# ind_8700.net
KiCad netlist of a schematic drawn in Altium Designer
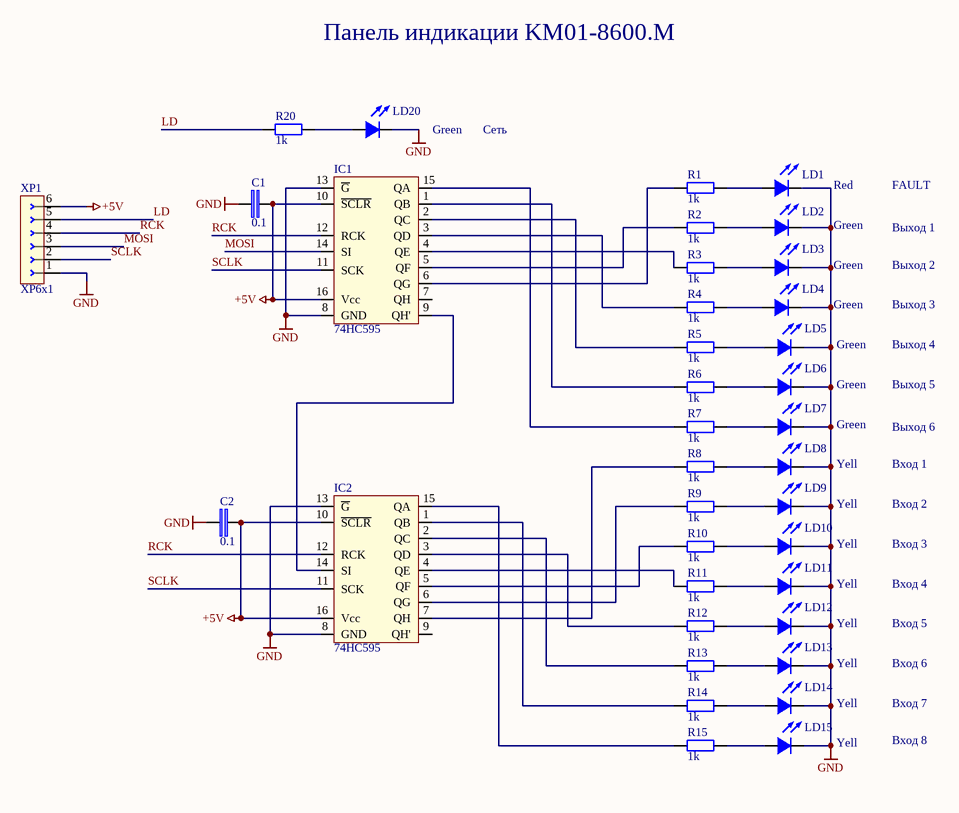
[diagram p0: ind_8700.SchDoc]

(export (version "E")
  (design (tool "Eeschema 10.0.6"))
  (components
    (comp (ref "C1") (value "0.1") (footprint "CAPC2113X13N_0805") (libsource (lib "Lib_my1") (part "cap_1")))
    (comp (ref "C2") (value "0.1") (footprint "CAPC2113X13N_0805") (libsource (lib "Lib_my1") (part "cap_1")))
    (comp (ref "IC1")
      (value "74HC595")
      (footprint "SOIC_16_74hc")
      (libsource (lib "Lib_my1") (part "74hc595_1"))
    )
    (comp (ref "IC2")
      (value "74HC595")
      (footprint "SOIC_16_74hc")
      (libsource (lib "Lib_my1") (part "74hc595_1"))
    )
    (comp (ref "LD1") (value "Red") (footprint "LED_3") (libsource (lib "Lib_my1") (part "LED_1")))
    (comp (ref "LD2") (value "Green") (footprint "LED_3") (libsource (lib "Lib_my1") (part "LED_1")))
    (comp (ref "LD3") (value "Green") (footprint "LED_3") (libsource (lib "Lib_my1") (part "LED_1")))
    (comp (ref "LD4") (value "Green") (footprint "LED_3") (libsource (lib "Lib_my1") (part "LED_1")))
    (comp (ref "LD5") (value "Green") (footprint "LED_3") (libsource (lib "Lib_my1") (part "LED_1")))
    (comp (ref "LD6") (value "Green") (footprint "LED_3") (libsource (lib "Lib_my1") (part "LED_1")))
    (comp (ref "LD7") (value "Green") (footprint "LED_3") (libsource (lib "Lib_my1") (part "LED_1")))
    (comp (ref "LD8") (value "Yell") (footprint "LED_3") (libsource (lib "Lib_my1") (part "LED_1")))
    (comp (ref "LD9") (value "Yell") (footprint "LED_3") (libsource (lib "Lib_my1") (part "LED_1")))
    (comp (ref "LD10") (value "Yell") (footprint "LED_3") (libsource (lib "Lib_my1") (part "LED_1")))
    (comp (ref "LD11") (value "Yell") (footprint "LED_3") (libsource (lib "Lib_my1") (part "LED_1")))
    (comp (ref "LD12") (value "Yell") (footprint "LED_3") (libsource (lib "Lib_my1") (part "LED_1")))
    (comp (ref "LD13") (value "Yell") (footprint "LED_3") (libsource (lib "Lib_my1") (part "LED_1")))
    (comp (ref "LD14") (value "Yell") (footprint "LED_3") (libsource (lib "Lib_my1") (part "LED_1")))
    (comp (ref "LD15") (value "Yell") (footprint "LED_3") (libsource (lib "Lib_my1") (part "LED_1")))
    (comp (ref "LD20") (value "Green") (footprint "LED_3") (libsource (lib "Lib_my1") (part "LED_1")))
    (comp (ref "R1") (value "1k") (footprint "RESC2113X0805N") (libsource (lib "Lib_my1") (part "rez_1")))
    (comp (ref "R2") (value "1k") (footprint "RESC2113X0805N") (libsource (lib "Lib_my1") (part "rez_1")))
    (comp (ref "R3") (value "1k") (footprint "RESC2113X0805N") (libsource (lib "Lib_my1") (part "rez_1")))
    (comp (ref "R4") (value "1k") (footprint "RESC2113X0805N") (libsource (lib "Lib_my1") (part "rez_1")))
    (comp (ref "R5") (value "1k") (footprint "RESC2113X0805N") (libsource (lib "Lib_my1") (part "rez_1")))
    (comp (ref "R6") (value "1k") (footprint "RESC2113X0805N") (libsource (lib "Lib_my1") (part "rez_1")))
    (comp (ref "R7") (value "1k") (footprint "RESC2113X0805N") (libsource (lib "Lib_my1") (part "rez_1")))
    (comp (ref "R8") (value "1k") (footprint "RESC2113X0805N") (libsource (lib "Lib_my1") (part "rez_1")))
    (comp (ref "R9") (value "1k") (footprint "RESC2113X0805N") (libsource (lib "Lib_my1") (part "rez_1")))
    (comp (ref "R10") (value "1k") (footprint "RESC2113X0805N") (libsource (lib "Lib_my1") (part "rez_1")))
    (comp (ref "R11") (value "1k") (footprint "RESC2113X0805N") (libsource (lib "Lib_my1") (part "rez_1")))
    (comp (ref "R12") (value "1k") (footprint "RESC2113X0805N") (libsource (lib "Lib_my1") (part "rez_1")))
    (comp (ref "R13") (value "1k") (footprint "RESC2113X0805N") (libsource (lib "Lib_my1") (part "rez_1")))
    (comp (ref "R14") (value "1k") (footprint "RESC2113X0805N") (libsource (lib "Lib_my1") (part "rez_1")))
    (comp (ref "R15") (value "1k") (footprint "RESC2113X0805N") (libsource (lib "Lib_my1") (part "rez_1")))
    (comp (ref "R20") (value "1k") (footprint "RESC2113X0805N") (libsource (lib "Lib_my1") (part "rez_1")))
    (comp (ref "XP1")
      (value "XP6x1")
      (footprint "Connect6_1")
      (libsource (lib "Lib_my1") (part "Connect6_1"))
    )
  )
  (nets
    (net (code "1") (name "+5V") (class "Default")
      (node (ref "C1") (pin "2") (pinfunction "2_2") (pintype "passive"))
      (node (ref "C2") (pin "2") (pinfunction "2_2") (pintype "passive"))
      (node (ref "IC1") (pin "10") (pinfunction "~{SCLR}_10") (pintype "passive"))
      (node (ref "IC1") (pin "16") (pinfunction "Vcc_16") (pintype "passive"))
      (node (ref "IC2") (pin "10") (pinfunction "~{SCLR}_10") (pintype "passive"))
      (node (ref "IC2") (pin "16") (pinfunction "Vcc_16") (pintype "passive"))
      (node (ref "XP1") (pin "6") (pinfunction "6_6") (pintype "passive"))
    )
    (net (code "2") (name "/LD") (class "Default")
      (node (ref "R20") (pin "2") (pinfunction "2_2") (pintype "passive"))
      (node (ref "XP1") (pin "5") (pinfunction "5_5") (pintype "passive"))
    )
    (net (code "3") (name "/MOSI") (class "Default")
      (node (ref "IC1") (pin "14") (pinfunction "SI_14") (pintype "passive"))
      (node (ref "XP1") (pin "3") (pinfunction "3_3") (pintype "passive"))
    )
    (net (code "4") (name "/RCK") (class "Default")
      (node (ref "IC1") (pin "12") (pinfunction "RCK_12") (pintype "passive"))
      (node (ref "IC2") (pin "12") (pinfunction "RCK_12") (pintype "passive"))
      (node (ref "XP1") (pin "4") (pinfunction "4_4") (pintype "passive"))
    )
    (net (code "5") (name "/SCLK") (class "Default")
      (node (ref "IC1") (pin "11") (pinfunction "SCK_11") (pintype "passive"))
      (node (ref "IC2") (pin "11") (pinfunction "SCK_11") (pintype "passive"))
      (node (ref "XP1") (pin "2") (pinfunction "2_2") (pintype "passive"))
    )
    (net (code "6") (name "GND") (class "Default")
      (node (ref "C1") (pin "1") (pinfunction "1_1") (pintype "passive"))
      (node (ref "C2") (pin "1") (pinfunction "1_1") (pintype "passive"))
      (node (ref "IC1") (pin "13") (pinfunction "G_13") (pintype "passive"))
      (node (ref "IC1") (pin "8") (pinfunction "GND_8") (pintype "passive"))
      (node (ref "IC2") (pin "13") (pinfunction "G_13") (pintype "passive"))
      (node (ref "IC2") (pin "8") (pinfunction "GND_8") (pintype "passive"))
      (node (ref "LD1") (pin "2") (pinfunction "2_2") (pintype "passive"))
      (node (ref "LD10") (pin "2") (pinfunction "2_2") (pintype "passive"))
      (node (ref "LD11") (pin "2") (pinfunction "2_2") (pintype "passive"))
      (node (ref "LD12") (pin "2") (pinfunction "2_2") (pintype "passive"))
      (node (ref "LD13") (pin "2") (pinfunction "2_2") (pintype "passive"))
      (node (ref "LD14") (pin "2") (pinfunction "2_2") (pintype "passive"))
      (node (ref "LD15") (pin "2") (pinfunction "2_2") (pintype "passive"))
      (node (ref "LD2") (pin "2") (pinfunction "2_2") (pintype "passive"))
      (node (ref "LD20") (pin "2") (pinfunction "2_2") (pintype "passive"))
      (node (ref "LD3") (pin "2") (pinfunction "2_2") (pintype "passive"))
      (node (ref "LD4") (pin "2") (pinfunction "2_2") (pintype "passive"))
      (node (ref "LD5") (pin "2") (pinfunction "2_2") (pintype "passive"))
      (node (ref "LD6") (pin "2") (pinfunction "2_2") (pintype "passive"))
      (node (ref "LD7") (pin "2") (pinfunction "2_2") (pintype "passive"))
      (node (ref "LD8") (pin "2") (pinfunction "2_2") (pintype "passive"))
      (node (ref "LD9") (pin "2") (pinfunction "2_2") (pintype "passive"))
      (node (ref "XP1") (pin "1") (pinfunction "1_1") (pintype "passive"))
    )
    (net (code "7") (name "Net-(IC1-QA)") (class "Default")
      (node (ref "IC1") (pin "15") (pinfunction "QA_15") (pintype "passive"))
      (node (ref "R7") (pin "2") (pinfunction "2_2") (pintype "passive"))
    )
    (net (code "8") (name "Net-(IC1-QB)") (class "Default")
      (node (ref "IC1") (pin "1") (pinfunction "QB_1") (pintype "passive"))
      (node (ref "R6") (pin "2") (pinfunction "2_2") (pintype "passive"))
    )
    (net (code "9") (name "Net-(IC1-QC)") (class "Default")
      (node (ref "IC1") (pin "2") (pinfunction "QC_2") (pintype "passive"))
      (node (ref "R5") (pin "2") (pinfunction "2_2") (pintype "passive"))
    )
    (net (code "10") (name "Net-(IC1-QD)") (class "Default")
      (node (ref "IC1") (pin "3") (pinfunction "QD_3") (pintype "passive"))
      (node (ref "R4") (pin "2") (pinfunction "2_2") (pintype "passive"))
    )
    (net (code "11") (name "Net-(IC1-QE)") (class "Default")
      (node (ref "IC1") (pin "4") (pinfunction "QE_4") (pintype "passive"))
      (node (ref "R3") (pin "2") (pinfunction "2_2") (pintype "passive"))
    )
    (net (code "12") (name "Net-(IC1-QF)") (class "Default")
      (node (ref "IC1") (pin "5") (pinfunction "QF_5") (pintype "passive"))
      (node (ref "R2") (pin "2") (pinfunction "2_2") (pintype "passive"))
    )
    (net (code "13") (name "Net-(IC1-QG)") (class "Default")
      (node (ref "IC1") (pin "6") (pinfunction "QG_6") (pintype "passive"))
      (node (ref "R1") (pin "2") (pinfunction "2_2") (pintype "passive"))
    )
    (net (code "14") (name "Net-(IC1-QH')") (class "Default")
      (node (ref "IC1") (pin "9") (pinfunction "QH'_9") (pintype "passive"))
      (node (ref "IC2") (pin "14") (pinfunction "SI_14") (pintype "passive"))
    )
    (net (code "15") (name "Net-(IC2-QA)") (class "Default")
      (node (ref "IC2") (pin "15") (pinfunction "QA_15") (pintype "passive"))
      (node (ref "R15") (pin "2") (pinfunction "2_2") (pintype "passive"))
    )
    (net (code "16") (name "Net-(IC2-QB)") (class "Default")
      (node (ref "IC2") (pin "1") (pinfunction "QB_1") (pintype "passive"))
      (node (ref "R14") (pin "2") (pinfunction "2_2") (pintype "passive"))
    )
    (net (code "17") (name "Net-(IC2-QC)") (class "Default")
      (node (ref "IC2") (pin "2") (pinfunction "QC_2") (pintype "passive"))
      (node (ref "R13") (pin "2") (pinfunction "2_2") (pintype "passive"))
    )
    (net (code "18") (name "Net-(IC2-QD)") (class "Default")
      (node (ref "IC2") (pin "3") (pinfunction "QD_3") (pintype "passive"))
      (node (ref "R12") (pin "2") (pinfunction "2_2") (pintype "passive"))
    )
    (net (code "19") (name "Net-(IC2-QE)") (class "Default")
      (node (ref "IC2") (pin "4") (pinfunction "QE_4") (pintype "passive"))
      (node (ref "R11") (pin "2") (pinfunction "2_2") (pintype "passive"))
    )
    (net (code "20") (name "Net-(IC2-QF)") (class "Default")
      (node (ref "IC2") (pin "5") (pinfunction "QF_5") (pintype "passive"))
      (node (ref "R10") (pin "2") (pinfunction "2_2") (pintype "passive"))
    )
    (net (code "21") (name "Net-(IC2-QG)") (class "Default")
      (node (ref "IC2") (pin "6") (pinfunction "QG_6") (pintype "passive"))
      (node (ref "R9") (pin "2") (pinfunction "2_2") (pintype "passive"))
    )
    (net (code "22") (name "Net-(IC2-QH)") (class "Default")
      (node (ref "IC2") (pin "7") (pinfunction "QH_7") (pintype "passive"))
      (node (ref "R8") (pin "2") (pinfunction "2_2") (pintype "passive"))
    )
    (net (code "23") (name "Net-(LD1-Pad1)") (class "Default")
      (node (ref "LD1") (pin "1") (pinfunction "1_1") (pintype "passive"))
      (node (ref "R1") (pin "1") (pinfunction "1_1") (pintype "passive"))
    )
    (net (code "24") (name "Net-(LD2-Pad1)") (class "Default")
      (node (ref "LD2") (pin "1") (pinfunction "1_1") (pintype "passive"))
      (node (ref "R2") (pin "1") (pinfunction "1_1") (pintype "passive"))
    )
    (net (code "25") (name "Net-(LD3-Pad1)") (class "Default")
      (node (ref "LD3") (pin "1") (pinfunction "1_1") (pintype "passive"))
      (node (ref "R3") (pin "1") (pinfunction "1_1") (pintype "passive"))
    )
    (net (code "26") (name "Net-(LD4-Pad1)") (class "Default")
      (node (ref "LD4") (pin "1") (pinfunction "1_1") (pintype "passive"))
      (node (ref "R4") (pin "1") (pinfunction "1_1") (pintype "passive"))
    )
    (net (code "27") (name "Net-(LD5-Pad1)") (class "Default")
      (node (ref "LD5") (pin "1") (pinfunction "1_1") (pintype "passive"))
      (node (ref "R5") (pin "1") (pinfunction "1_1") (pintype "passive"))
    )
    (net (code "28") (name "Net-(LD6-Pad1)") (class "Default")
      (node (ref "LD6") (pin "1") (pinfunction "1_1") (pintype "passive"))
      (node (ref "R6") (pin "1") (pinfunction "1_1") (pintype "passive"))
    )
    (net (code "29") (name "Net-(LD7-Pad1)") (class "Default")
      (node (ref "LD7") (pin "1") (pinfunction "1_1") (pintype "passive"))
      (node (ref "R7") (pin "1") (pinfunction "1_1") (pintype "passive"))
    )
    (net (code "30") (name "Net-(LD8-Pad1)") (class "Default")
      (node (ref "LD8") (pin "1") (pinfunction "1_1") (pintype "passive"))
      (node (ref "R8") (pin "1") (pinfunction "1_1") (pintype "passive"))
    )
    (net (code "31") (name "Net-(LD9-Pad1)") (class "Default")
      (node (ref "LD9") (pin "1") (pinfunction "1_1") (pintype "passive"))
      (node (ref "R9") (pin "1") (pinfunction "1_1") (pintype "passive"))
    )
    (net (code "32") (name "Net-(LD10-Pad1)") (class "Default")
      (node (ref "LD10") (pin "1") (pinfunction "1_1") (pintype "passive"))
      (node (ref "R10") (pin "1") (pinfunction "1_1") (pintype "passive"))
    )
    (net (code "33") (name "Net-(LD11-Pad1)") (class "Default")
      (node (ref "LD11") (pin "1") (pinfunction "1_1") (pintype "passive"))
      (node (ref "R11") (pin "1") (pinfunction "1_1") (pintype "passive"))
    )
    (net (code "34") (name "Net-(LD12-Pad1)") (class "Default")
      (node (ref "LD12") (pin "1") (pinfunction "1_1") (pintype "passive"))
      (node (ref "R12") (pin "1") (pinfunction "1_1") (pintype "passive"))
    )
    (net (code "35") (name "Net-(LD13-Pad1)") (class "Default")
      (node (ref "LD13") (pin "1") (pinfunction "1_1") (pintype "passive"))
      (node (ref "R13") (pin "1") (pinfunction "1_1") (pintype "passive"))
    )
    (net (code "36") (name "Net-(LD14-Pad1)") (class "Default")
      (node (ref "LD14") (pin "1") (pinfunction "1_1") (pintype "passive"))
      (node (ref "R14") (pin "1") (pinfunction "1_1") (pintype "passive"))
    )
    (net (code "37") (name "Net-(LD15-Pad1)") (class "Default")
      (node (ref "LD15") (pin "1") (pinfunction "1_1") (pintype "passive"))
      (node (ref "R15") (pin "1") (pinfunction "1_1") (pintype "passive"))
    )
    (net (code "38") (name "Net-(LD20-Pad1)") (class "Default")
      (node (ref "LD20") (pin "1") (pinfunction "1_1") (pintype "passive"))
      (node (ref "R20") (pin "1") (pinfunction "1_1") (pintype "passive"))
    )
    (net (code "39") (name "unconnected-(IC1-QH-Pad7)") (class "Default")
      (node (ref "IC1") (pin "7") (pinfunction "QH_7") (pintype "passive"))
    )
    (net (code "40") (name "unconnected-(IC2-QH'-Pad9)") (class "Default")
      (node (ref "IC2") (pin "9") (pinfunction "QH'_9") (pintype "passive"))
    )
  )
)
